# 5V.net
KiCad netlist of a schematic drawn in Altium Designer
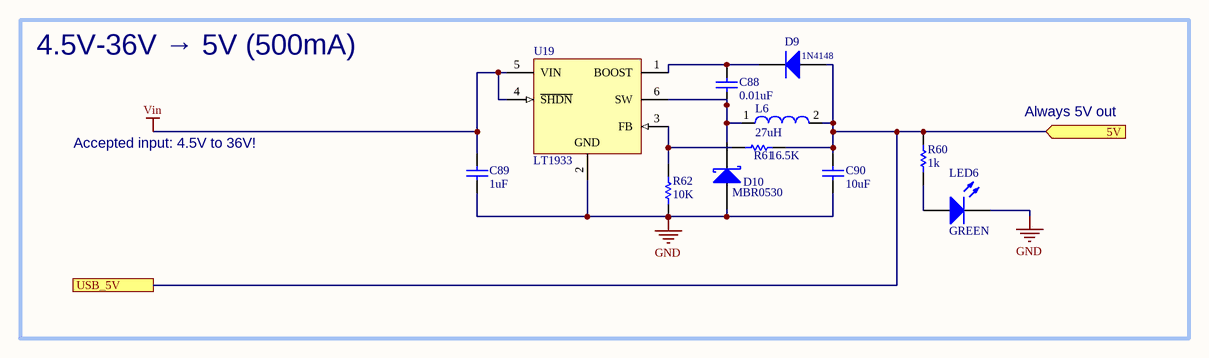
[diagram p0: 5V.SchDoc]

(export (version "E")
  (design (tool "Eeschema 10.0.6"))
  (components
    (comp (ref "C88")
      (value "0.01uF")
      (footprint "CAPC1608X87X35NL15T15")
      (description "0.01uF 0603 50V")
      (fields (field (name "MANUFACTURER") "Kemet") (field (name "PART NUMBER") "C0603C101J5GACTU"))
      (libsource (lib "Altium Content Vault") (part "CAP"))
    )
    (comp (ref "C89")
      (value "1uF")
      (footprint "CAPC1608X87X35NL15T15")
      (description "1uF 0603 50V")
      (fields (field (name "MANUFACTURER") "Kemet") (field (name "PART NUMBER") "C0603C101J5GACTU"))
      (libsource (lib "Altium Content Vault") (part "CAP"))
    )
    (comp (ref "C90")
      (value "10uF")
      (footprint "CAPC1608X90X35NL10T15")
      (fields (field (name "PART NUMBER") "GRM188R60J106ME47D") (field (name "MANUFACTURER") "Murata"))
      (libsource (lib "Altium Content Vault") (part "CAP"))
    )
    (comp (ref "D9")
      (value "1N4148")
      (footprint "DIOD-SOD123-2_V")
      (description "Fast Switching Diode, 100 V, 0.15 A, -65 to 150 degC, 2-Pin?SOD123, RoHS, Tape and Reel")
      (fields (field (name "MANUFACTURER") "DiodesIncorporated"))
      (libsource (lib "Altium Content Vault") (part "D-AK-2"))
    )
    (comp (ref "D10")
      (value "MBR0530")
      (footprint "FAIR-SOD123-2_V")
      (description "Diode Schottky 30V 0.5A 2-Pin SOD-123 T/R")
      (fields (field (name "MANUFACTURER") "Fairchild"))
      (libsource (lib "Altium Content Vault") (part "DSKY-AK-2"))
    )
    (comp (ref "L6")
      (value "27uH")
      (footprint "WE-PD-M-PB")
      (description "SMD-Shielded Power Inductor WE-PD, L=27 µH")
      (fields (field (name "MANUFACTURER") "Wuerth Elektronik") (field (name "PARTNUMBER") "7447779127"))
      (libsource (lib "Altium Content Vault") (part "PAS-IND-INDUCTOR-2"))
    )
    (comp (ref "LED6")
      (value "GREEN")
      (footprint "0603_A")
      (description "SMD mono-color Chip LED, WL-SMCW, Bright Green")
      (fields (field (name "PARTNUMBER") "150060VS75000") (field (name "MANUFACTURER") "Wuerth Elektronik"))
      (libsource (lib "Altium Content Vault") (part "WE-LED_K1A2-2"))
    )
    (comp (ref "R60")
      (value "1k")
      (footprint "RESC0603(1608)_L")
      (description "1k 0.1W 5% 0603 (1608 Metric)  SMD")
      (fields (field (name "TOLERANCE") "5 %") (field (name "POWER") "0.1 W"))
      (libsource (lib "Altium Content Vault") (part "RES"))
    )
    (comp (ref "R61")
      (value "16.5K")
      (footprint "RESC0603(1608)_L")
      (description "16.5K 0.1W 5% 0603 (1608 Metric)  SMD")
      (fields (field (name "TOLERANCE") "5 %") (field (name "POWER") "0.1 W"))
      (libsource (lib "Altium Content Vault") (part "RES"))
    )
    (comp (ref "R62")
      (value "10K")
      (footprint "RESC0603(1608)_L")
      (description "10K 0.1W 5% 0603 (1608 Metric)  SMD")
      (fields (field (name "TOLERANCE") "5 %") (field (name "POWER") "0.1 W"))
      (libsource (lib "Altium Content Vault") (part "RES"))
    )
    (comp (ref "U19")
      (value "LT1933")
      (footprint "LT-S6-6-SOT-23_L")
      (fields (field (name "PARTNUMBER") "LT1933ES6#TRPBF") (field (name "MANUFACTURER") "Linear Technology"))
      (libsource (lib "Altium Content Vault") (part "LT-LT1616_1933_1934_1934-1"))
    )
  )
  (nets
    (net (code "1") (name "/5V") (class "Default")
      (node (ref "C90") (pin "2") (pinfunction "2_2") (pintype "passive"))
      (node (ref "D9") (pin "1") (pinfunction "A_1") (pintype "passive"))
      (node (ref "L6") (pin "2") (pinfunction "2_2") (pintype "passive"))
      (node (ref "R60") (pin "2") (pinfunction "2_2") (pintype "passive"))
      (node (ref "R61") (pin "1") (pinfunction "1_1") (pintype "passive"))
    )
    (net (code "2") (name "GND") (class "Default")
      (node (ref "C89") (pin "1") (pinfunction "1_1") (pintype "passive"))
      (node (ref "C90") (pin "1") (pinfunction "1_1") (pintype "passive"))
      (node (ref "D10") (pin "1") (pinfunction "A_1") (pintype "passive"))
      (node (ref "LED6") (pin "1") (pinfunction "K_1") (pintype "passive"))
      (node (ref "R62") (pin "1") (pinfunction "1_1") (pintype "passive"))
      (node (ref "U19") (pin "2") (pinfunction "GND_2") (pintype "power_in"))
    )
    (net (code "3") (name "Net-(D9-K)") (class "Default")
      (node (ref "C88") (pin "2") (pinfunction "2_2") (pintype "passive"))
      (node (ref "D9") (pin "2") (pinfunction "K_2") (pintype "passive"))
      (node (ref "U19") (pin "1") (pinfunction "BOOST_1") (pintype "passive"))
    )
    (net (code "4") (name "Net-(D10-K)") (class "Default")
      (node (ref "C88") (pin "1") (pinfunction "1_1") (pintype "passive"))
      (node (ref "D10") (pin "2") (pinfunction "K_2") (pintype "passive"))
      (node (ref "L6") (pin "1") (pinfunction "1_1") (pintype "passive"))
      (node (ref "U19") (pin "6") (pinfunction "SW_6") (pintype "power_in"))
    )
    (net (code "5") (name "Net-(LED6-A)") (class "Default")
      (node (ref "LED6") (pin "2") (pinfunction "A_2") (pintype "passive"))
      (node (ref "R60") (pin "1") (pinfunction "1_1") (pintype "passive"))
    )
    (net (code "6") (name "Net-(U19-FB)") (class "Default")
      (node (ref "R61") (pin "2") (pinfunction "2_2") (pintype "passive"))
      (node (ref "R62") (pin "2") (pinfunction "2_2") (pintype "passive"))
      (node (ref "U19") (pin "3") (pinfunction "FB_3") (pintype "input"))
    )
    (net (code "7") (name "Vin") (class "Default")
      (node (ref "C89") (pin "2") (pinfunction "2_2") (pintype "passive"))
      (node (ref "U19") (pin "4") (pinfunction "~{SHDN}_4") (pintype "input"))
      (node (ref "U19") (pin "5") (pinfunction "VIN_5") (pintype "power_in"))
    )
  )
)
